# ProtoSnap-Pro_Mini.net
KiCad netlist of a schematic drawn in EAGLE
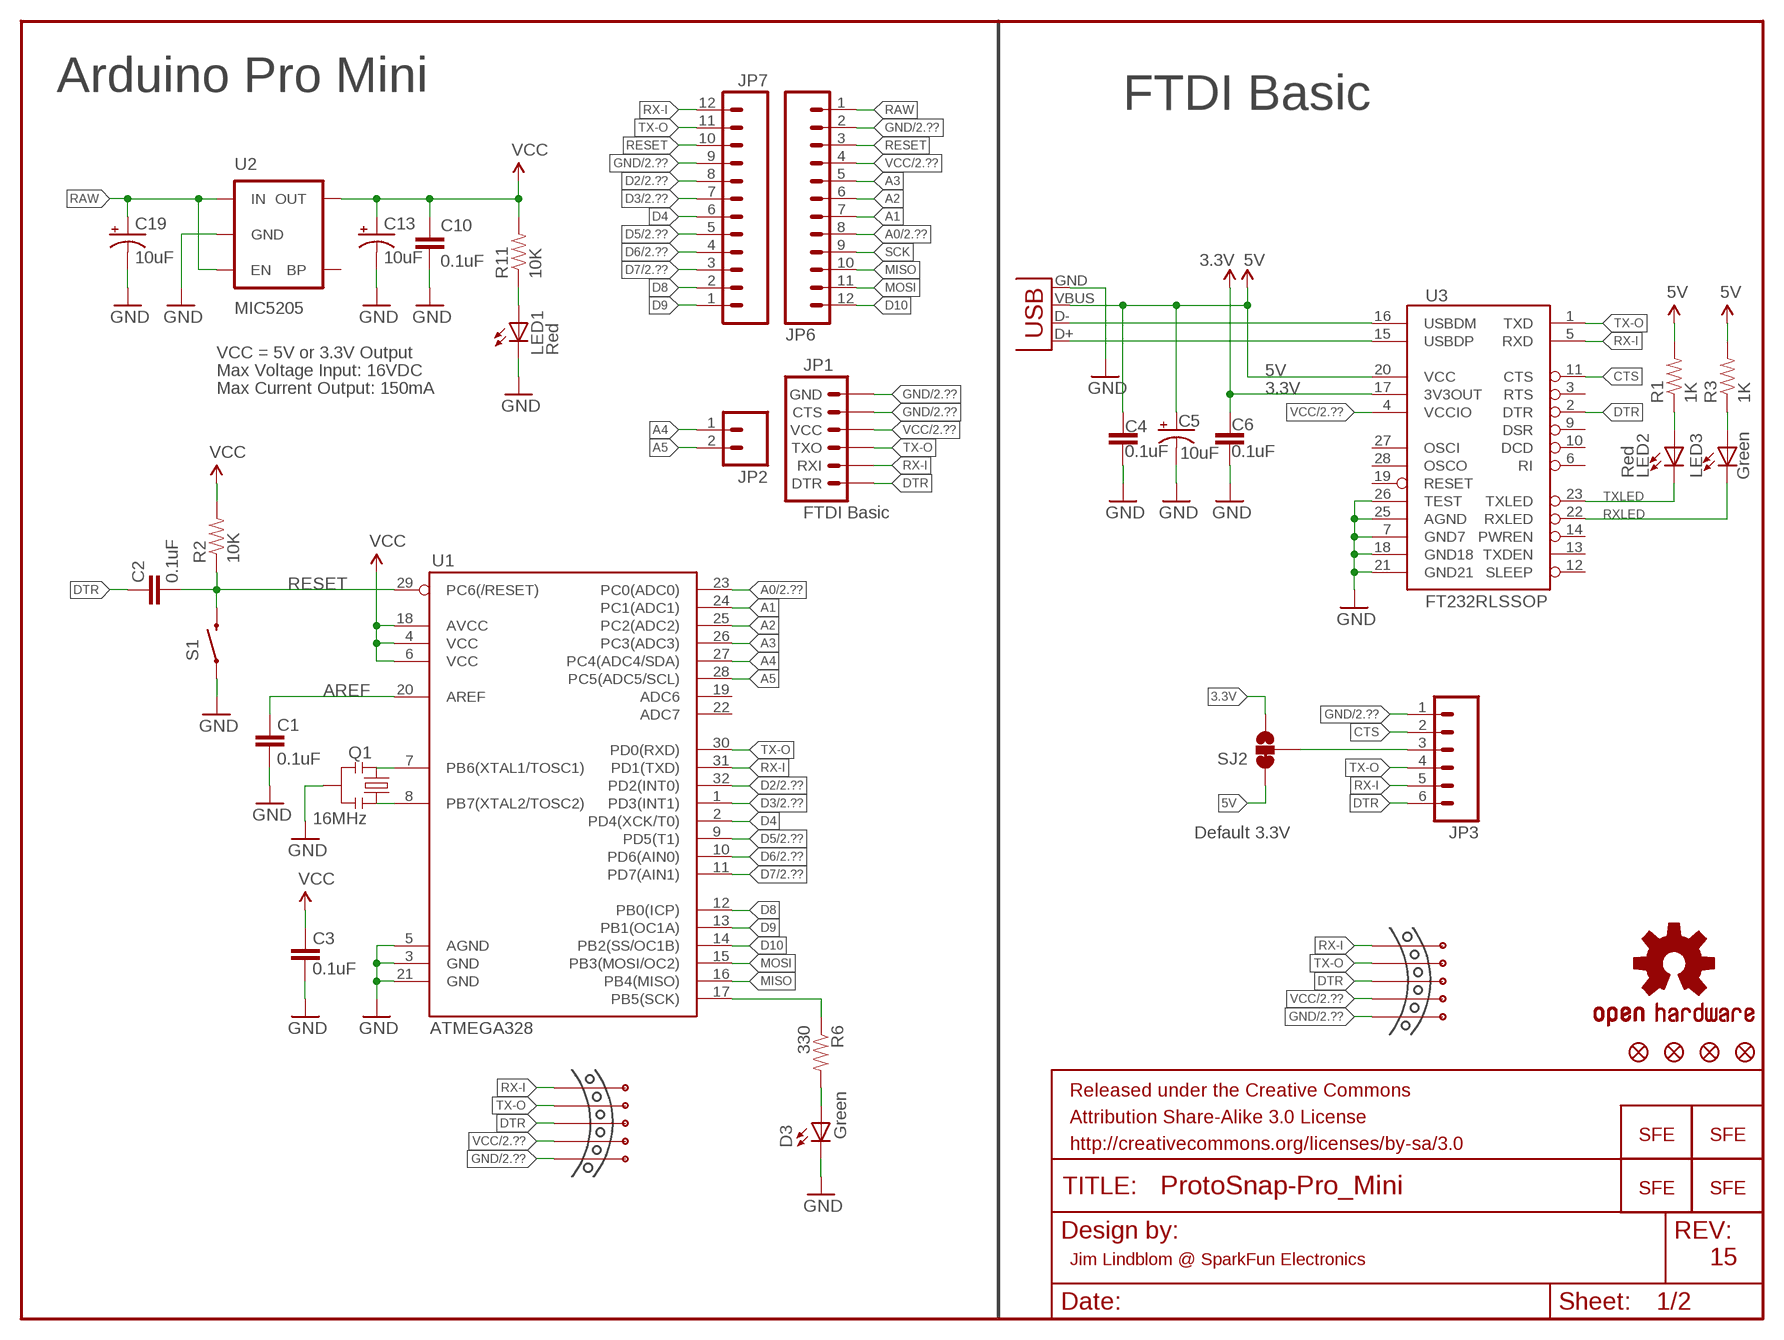
[diagram p0: schematic, sheet 1]
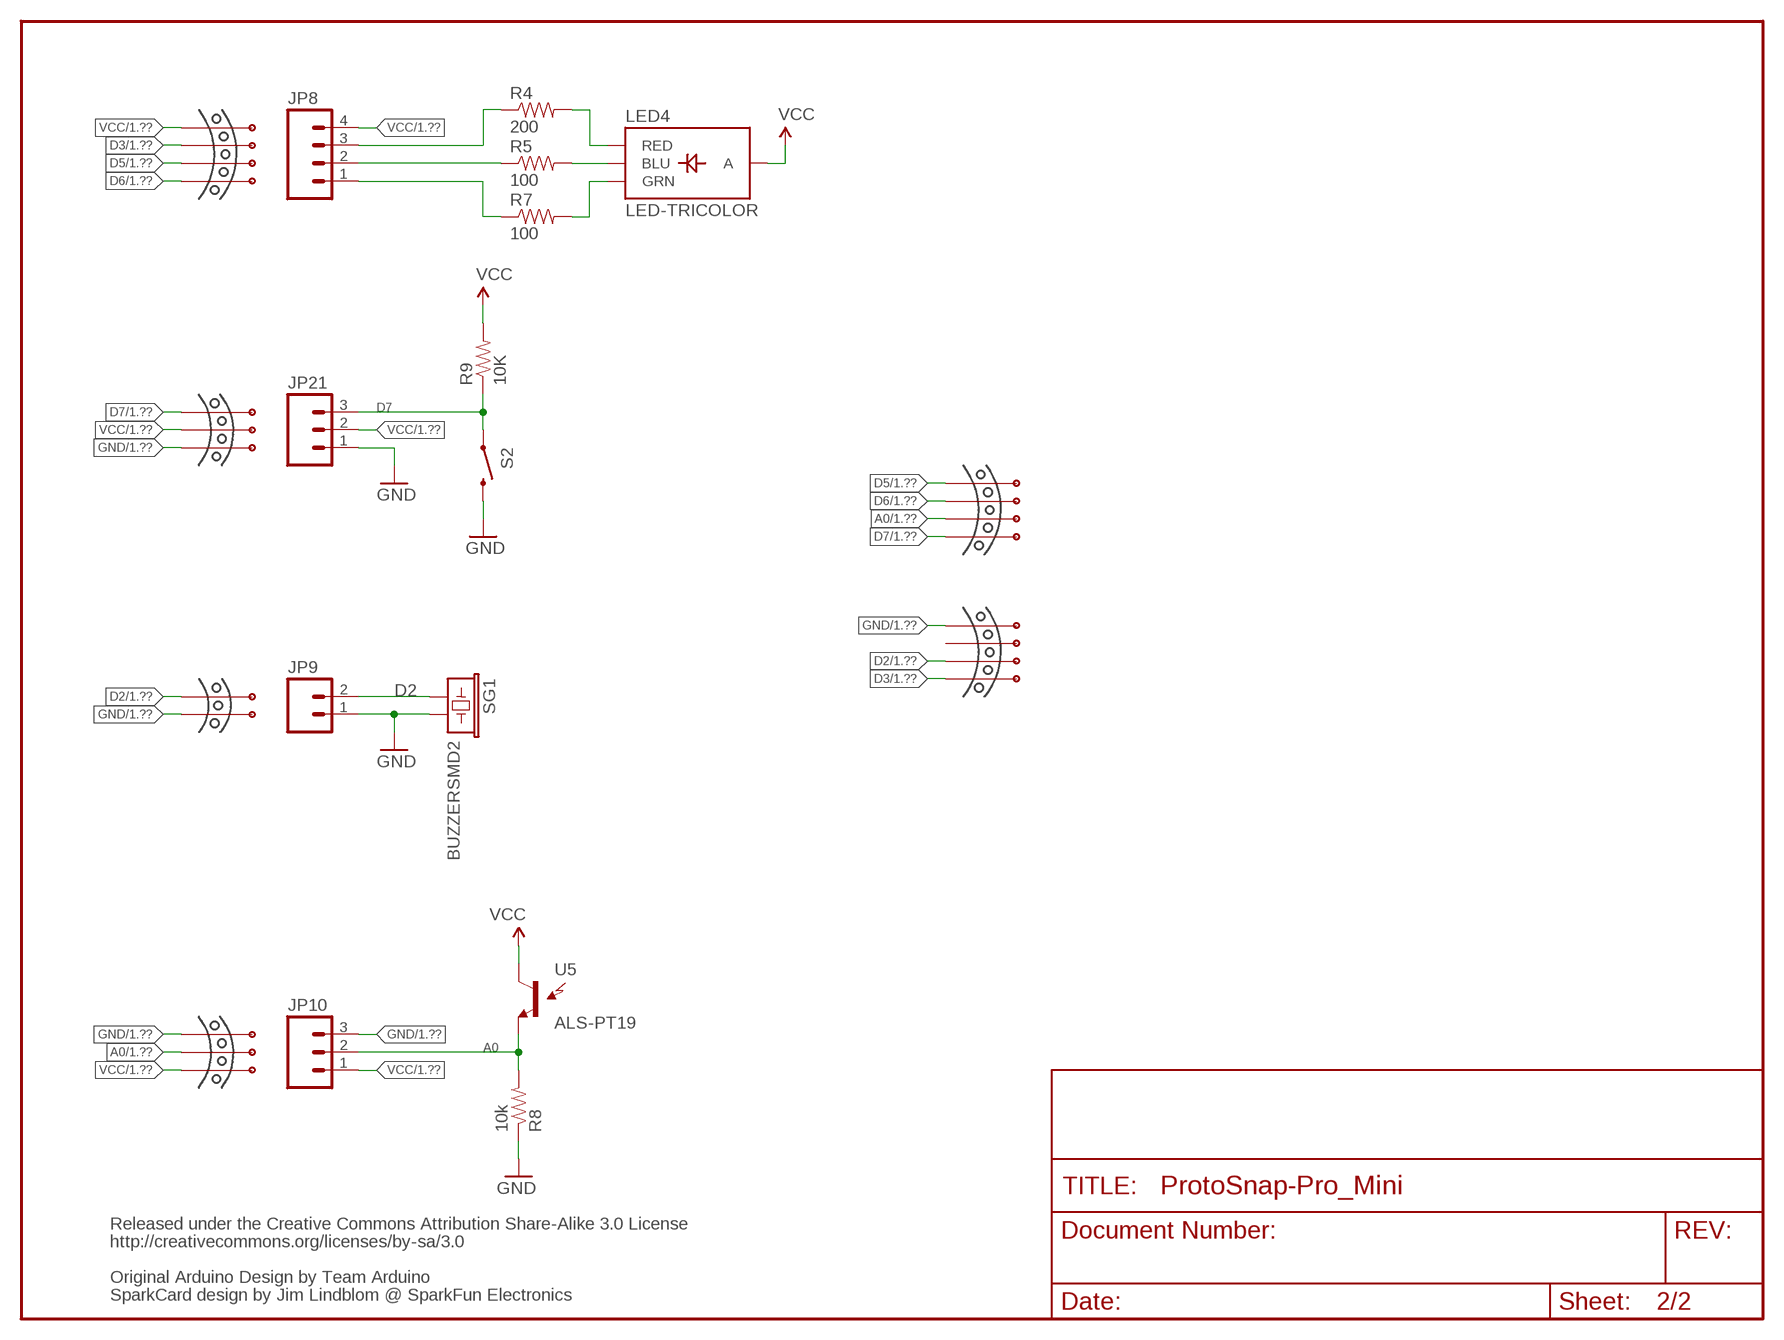
[diagram p1: schematic, sheet 2]

(export (version "E")
  (design (tool "Eeschema 10.0.6"))
  (components
    (comp (ref "C1")
      (value "0.1uF")
      (footprint "eagle-import:0603-CAP")
      (libsource (lib "eagle-import") (part "CAP0603-CAP"))
    )
    (comp (ref "C2")
      (value "0.1uF")
      (footprint "eagle-import:0603-CAP")
      (libsource (lib "eagle-import") (part "CAP0603-CAP"))
    )
    (comp (ref "C3")
      (value "0.1uF")
      (footprint "eagle-import:0603-CAP")
      (libsource (lib "eagle-import") (part "CAP0603-CAP"))
    )
    (comp (ref "C4")
      (value "0.1uF")
      (footprint "eagle-import:0603-CAP")
      (libsource (lib "eagle-import") (part "CAP0603-CAP"))
    )
    (comp (ref "C5")
      (value "10uF")
      (footprint "eagle-import:EIA3216")
      (libsource (lib "eagle-import") (part "CAP_POL1206"))
    )
    (comp (ref "C6")
      (value "0.1uF")
      (footprint "eagle-import:0603-CAP")
      (libsource (lib "eagle-import") (part "CAP0603-CAP"))
    )
    (comp (ref "C10")
      (value "0.1uF")
      (footprint "eagle-import:0603-CAP")
      (libsource (lib "eagle-import") (part "CAP0603-CAP"))
    )
    (comp (ref "C13")
      (value "10uF")
      (footprint "eagle-import:EIA3216")
      (libsource (lib "eagle-import") (part "CAP_POL1206"))
    )
    (comp (ref "C19")
      (value "10uF")
      (footprint "eagle-import:EIA3216")
      (libsource (lib "eagle-import") (part "CAP_POL1206"))
    )
    (comp (ref "D3")
      (value "Green")
      (footprint "eagle-import:0603-LED-ALT1")
      (libsource (lib "eagle-import") (part "LEDLED-ALT1"))
    )
    (comp (ref "FRAME1")
      (value "FRAME-LETTER")
      (footprint "eagle-import:CREATIVE_COMMONS")
      (libsource (lib "eagle-import") (part "SparkFun-Aesthetics_FRAME-LETTER"))
    )
    (comp (ref "JP1")
      (value "FTDI Basic")
      (footprint "eagle-import:1X06")
      (libsource (lib "eagle-import") (part "ARDUINO_SERIAL_PROGRAMPTH"))
    )
    (comp (ref "JP2")
      (value "M02PTH")
      (footprint "eagle-import:1X02")
      (libsource (lib "eagle-import") (part "M02PTH"))
    )
    (comp (ref "JP3")
      (value "M06SIP")
      (footprint "eagle-import:1X06")
      (libsource (lib "eagle-import") (part "M06SIP"))
    )
    (comp (ref "JP4")
      (value "LOGO-SFENW2")
      (footprint "eagle-import:SFE-NEW-WEB")
      (libsource (lib "eagle-import") (part "LOGO-SFENW2"))
    )
    (comp (ref "JP6")
      (value "M12PTH")
      (footprint "eagle-import:1X12")
      (libsource (lib "eagle-import") (part "M12PTH"))
    )
    (comp (ref "JP7")
      (value "M12PTH")
      (footprint "eagle-import:1X12")
      (libsource (lib "eagle-import") (part "M12PTH"))
    )
    (comp (ref "JP15")
      (value "LOGO-SFESK")
      (footprint "eagle-import:SFE-LOGO-FLAME")
      (libsource (lib "eagle-import") (part "LOGO-SFESK"))
    )
    (comp (ref "JP16")
      (value "FIDUCIAL1X2.5")
      (footprint "eagle-import:FIDUCIAL-1X2.5")
      (libsource (lib "eagle-import") (part "FIDUCIAL1X2.5"))
    )
    (comp (ref "JP17")
      (value "LOGO-SFESK")
      (footprint "eagle-import:SFE-LOGO-FLAME")
      (libsource (lib "eagle-import") (part "LOGO-SFESK"))
    )
    (comp (ref "JP18")
      (value "LOGO-SFENEW")
      (footprint "eagle-import:SFE-NEW-WEBLOGO")
      (libsource (lib "eagle-import") (part "LOGO-SFENEW"))
    )
    (comp (ref "JP19")
      (value "FIDUCIAL1X2.5")
      (footprint "eagle-import:FIDUCIAL-1X2.5")
      (libsource (lib "eagle-import") (part "FIDUCIAL1X2.5"))
    )
    (comp (ref "JP20")
      (value "FIDUCIAL1X2.5")
      (footprint "eagle-import:FIDUCIAL-1X2.5")
      (libsource (lib "eagle-import") (part "FIDUCIAL1X2.5"))
    )
    (comp (ref "JP22")
      (value "FIDUCIAL1X2.5")
      (footprint "eagle-import:FIDUCIAL-1X2.5")
      (libsource (lib "eagle-import") (part "FIDUCIAL1X2.5"))
    )
    (comp (ref "LED1")
      (value "Red")
      (footprint "eagle-import:0603-LED-ALT1")
      (libsource (lib "eagle-import") (part "LEDLED-ALT1"))
    )
    (comp (ref "LED2")
      (value "Red")
      (footprint "eagle-import:0603-LED-ALT1")
      (libsource (lib "eagle-import") (part "LEDLED-ALT1"))
    )
    (comp (ref "LED3")
      (value "Green")
      (footprint "eagle-import:0603-LED-ALT1")
      (libsource (lib "eagle-import") (part "LEDLED-ALT1"))
    )
    (comp (ref "LOGO1")
      (value "OSHW-LOGOS")
      (footprint "eagle-import:OSHW-LOGO-S")
      (libsource (lib "eagle-import") (part "OSHW-LOGOS"))
    )
    (comp (ref "Q1")
      (value "16MHz")
      (footprint "eagle-import:RESONATOR-SMD-1_1")
      (libsource (lib "eagle-import") (part "RESONATOR1{colon}1"))
    )
    (comp (ref "R1")
      (value "1K")
      (footprint "eagle-import:0603-RES")
      (libsource (lib "eagle-import") (part "RESISTOR0603-RES"))
    )
    (comp (ref "R2")
      (value "10K")
      (footprint "eagle-import:0603-RES")
      (libsource (lib "eagle-import") (part "RESISTOR0603-RES"))
    )
    (comp (ref "R3")
      (value "1K")
      (footprint "eagle-import:0603-RES")
      (libsource (lib "eagle-import") (part "RESISTOR0603-RES"))
    )
    (comp (ref "R6")
      (value "330")
      (footprint "eagle-import:0603-RES")
      (libsource (lib "eagle-import") (part "RESISTOR0603-RES"))
    )
    (comp (ref "R11")
      (value "10K")
      (footprint "eagle-import:0603-RES")
      (libsource (lib "eagle-import") (part "RESISTOR0603-RES"))
    )
    (comp (ref "S1")
      (value "SWITCH-MOMENTARY-2SMD-ALT01")
      (footprint "eagle-import:TACTILE-SWITCH-SMD-ALT01")
      (libsource (lib "eagle-import") (part "SWITCH-MOMENTARY-2SMD-ALT01"))
    )
    (comp (ref "SJ2")
      (value "SOLDERJUMPER_2WAYS")
      (footprint "eagle-import:SJ_3")
      (libsource (lib "eagle-import") (part "SOLDERJUMPER_2WAYS"))
    )
    (comp (ref "U$22")
      (value "MOUSE-BITE-5")
      (footprint "eagle-import:MOUSE-BITE-5")
      (libsource (lib "eagle-import") (part "MOUSE-BITE-5"))
    )
    (comp (ref "U$23")
      (value "MOUSE-BITE-5")
      (footprint "eagle-import:MOUSE-BITE-5")
      (libsource (lib "eagle-import") (part "MOUSE-BITE-5"))
    )
    (comp (ref "U1")
      (value "ATMEGA328")
      (footprint "eagle-import:TQFP32-08")
      (libsource (lib "eagle-import") (part "ATMEGA168"))
    )
    (comp (ref "U2")
      (value "MIC5205")
      (footprint "eagle-import:SOT23-5")
      (libsource (lib "eagle-import") (part "V_REG_LDOSMD"))
    )
    (comp (ref "U3")
      (value "FT232RLSSOP")
      (footprint "eagle-import:SSOP28DB")
      (libsource (lib "eagle-import") (part "FT232RLSSOP"))
    )
    (comp (ref "X2")
      (value "USB-SMD-NS")
      (footprint "eagle-import:USB-MINIB-NOSTOP")
      (libsource (lib "eagle-import") (part "USB-SMD-NS"))
    )
    (comp (ref "JP8")
      (value "M04PTH")
      (footprint "eagle-import:1X04")
      (libsource (lib "eagle-import") (part "M04PTH"))
    )
    (comp (ref "JP9")
      (value "M02PTH")
      (footprint "eagle-import:1X02")
      (libsource (lib "eagle-import") (part "M02PTH"))
    )
    (comp (ref "JP10")
      (value "M03PTH")
      (footprint "eagle-import:1X03")
      (libsource (lib "eagle-import") (part "M03PTH"))
    )
    (comp (ref "JP21")
      (value "M03PTH")
      (footprint "eagle-import:1X03")
      (libsource (lib "eagle-import") (part "M03PTH"))
    )
    (comp (ref "LED4")
      (value "LED-TRICOLOR")
      (footprint "eagle-import:LED-TRICOLOR-SMD")
      (libsource (lib "eagle-import") (part "LED-TRICOLOR"))
    )
    (comp (ref "R4")
      (value "200")
      (footprint "eagle-import:0603-RES")
      (libsource (lib "eagle-import") (part "RESISTOR0603-RES"))
    )
    (comp (ref "R5")
      (value "100")
      (footprint "eagle-import:0603-RES")
      (libsource (lib "eagle-import") (part "RESISTOR0603-RES"))
    )
    (comp (ref "R7")
      (value "100")
      (footprint "eagle-import:0603-RES")
      (libsource (lib "eagle-import") (part "RESISTOR0603-RES"))
    )
    (comp (ref "R8")
      (value "10k")
      (footprint "eagle-import:0603-RES")
      (libsource (lib "eagle-import") (part "RESISTOR0603-RES"))
    )
    (comp (ref "R9")
      (value "10K")
      (footprint "eagle-import:0603-RES")
      (libsource (lib "eagle-import") (part "RESISTOR0603-RES"))
    )
    (comp (ref "S2")
      (value "SWITCH-MOMENTARY-2SMD-ALT01")
      (footprint "eagle-import:TACTILE-SWITCH-SMD-ALT01")
      (libsource (lib "eagle-import") (part "SWITCH-MOMENTARY-2SMD-ALT01"))
    )
    (comp (ref "SG1")
      (value "BUZZERSMD2")
      (footprint "eagle-import:BUZZER-CCV")
      (libsource (lib "eagle-import") (part "BUZZERSMD2"))
    )
    (comp (ref "U$2")
      (value "MOUSE-BITE-3")
      (footprint "eagle-import:MOUSE-BITE-3")
      (libsource (lib "eagle-import") (part "MOUSE-BITE-3"))
    )
    (comp (ref "U$7")
      (value "MOUSE-BITE-2")
      (footprint "eagle-import:MOUSE-BITE-2")
      (libsource (lib "eagle-import") (part "MOUSE-BITE-2"))
    )
    (comp (ref "U$8")
      (value "MOUSE-BITE-4")
      (footprint "eagle-import:MOUSE-BITE-4")
      (libsource (lib "eagle-import") (part "MOUSE-BITE-4"))
    )
    (comp (ref "U$9")
      (value "MOUSE-BITE-3")
      (footprint "eagle-import:MOUSE-BITE-3")
      (libsource (lib "eagle-import") (part "MOUSE-BITE-3"))
    )
    (comp (ref "U$13")
      (value "MOUSE-BITE-4")
      (footprint "eagle-import:MOUSE-BITE-4")
      (libsource (lib "eagle-import") (part "MOUSE-BITE-4"))
    )
    (comp (ref "U$14")
      (value "MOUSE-BITE-4")
      (footprint "eagle-import:MOUSE-BITE-4")
      (libsource (lib "eagle-import") (part "MOUSE-BITE-4"))
    )
    (comp (ref "U5")
      (value "ALS-PT19")
      (footprint "eagle-import:ALS-PT19")
      (libsource (lib "eagle-import") (part "LIGHTSENSORALS"))
    )
  )
  (nets
    (net (code "1") (name "3.3V") (class "Default")
      (node (ref "C6") (pin "1") (pinfunction "1_1") (pintype "passive"))
      (node (ref "SJ2") (pin "3") (pinfunction "3_3") (pintype "passive"))
      (node (ref "U3") (pin "17") (pinfunction "3V3OUT_17") (pintype "output"))
    )
    (net (code "2") (name "5V") (class "Default")
      (node (ref "C4") (pin "1") (pinfunction "1_1") (pintype "passive"))
      (node (ref "C5") (pin "A") (pinfunction "+_A") (pintype "passive"))
      (node (ref "R1") (pin "2") (pinfunction "2_2") (pintype "passive"))
      (node (ref "R3") (pin "2") (pinfunction "2_2") (pintype "passive"))
      (node (ref "SJ2") (pin "1") (pinfunction "1_1") (pintype "passive"))
      (node (ref "U3") (pin "20") (pinfunction "VCC_20") (pintype "power_in"))
      (node (ref "X2") (pin "VBUS") (pinfunction "VBUS_VBUS") (pintype "bidirectional"))
    )
    (net (code "3") (name "A0") (class "Default")
      (node (ref "JP10") (pin "2") (pinfunction "2_2") (pintype "passive"))
      (node (ref "JP6") (pin "8") (pinfunction "8_8") (pintype "passive"))
      (node (ref "R8") (pin "2") (pinfunction "2_2") (pintype "passive"))
      (node (ref "U$13") (pin "P$3") (pinfunction "P$3_P$3") (pintype "bidirectional"))
      (node (ref "U$9") (pin "P$2") (pinfunction "P$2_P$2") (pintype "bidirectional"))
      (node (ref "U1") (pin "23") (pinfunction "PC0(ADC0)_23") (pintype "bidirectional"))
      (node (ref "U5") (pin "E") (pinfunction "E1_E") (pintype "passive"))
    )
    (net (code "4") (name "A1") (class "Default")
      (node (ref "JP6") (pin "7") (pinfunction "7_7") (pintype "passive"))
      (node (ref "U1") (pin "24") (pinfunction "PC1(ADC1)_24") (pintype "bidirectional"))
    )
    (net (code "5") (name "A2") (class "Default")
      (node (ref "JP6") (pin "6") (pinfunction "6_6") (pintype "passive"))
      (node (ref "U1") (pin "25") (pinfunction "PC2(ADC2)_25") (pintype "bidirectional"))
    )
    (net (code "6") (name "A3") (class "Default")
      (node (ref "JP6") (pin "5") (pinfunction "5_5") (pintype "passive"))
      (node (ref "U1") (pin "26") (pinfunction "PC3(ADC3)_26") (pintype "bidirectional"))
    )
    (net (code "7") (name "A4") (class "Default")
      (node (ref "JP2") (pin "1") (pinfunction "1_1") (pintype "passive"))
      (node (ref "U1") (pin "27") (pinfunction "PC4(ADC4/SDA)_27") (pintype "bidirectional"))
    )
    (net (code "8") (name "A5") (class "Default")
      (node (ref "JP2") (pin "2") (pinfunction "2_2") (pintype "passive"))
      (node (ref "U1") (pin "28") (pinfunction "PC5(ADC5/SCL)_28") (pintype "bidirectional"))
    )
    (net (code "9") (name "AREF") (class "Default")
      (node (ref "C1") (pin "2") (pinfunction "2_2") (pintype "passive"))
      (node (ref "U1") (pin "20") (pinfunction "AREF_20") (pintype "bidirectional"))
    )
    (net (code "10") (name "CTS") (class "Default")
      (node (ref "JP3") (pin "2") (pinfunction "2_2") (pintype "passive"))
      (node (ref "U3") (pin "11") (pinfunction "CTS_11") (pintype "input"))
    )
    (net (code "11") (name "D2") (class "Default")
      (node (ref "JP7") (pin "8") (pinfunction "8_8") (pintype "passive"))
      (node (ref "JP9") (pin "2") (pinfunction "2_2") (pintype "passive"))
      (node (ref "SG1") (pin "+") (pinfunction "1_+") (pintype "passive"))
      (node (ref "U$14") (pin "P$3") (pinfunction "P$3_P$3") (pintype "bidirectional"))
      (node (ref "U$7") (pin "P$1") (pinfunction "P$1_P$1") (pintype "bidirectional"))
      (node (ref "U1") (pin "32") (pinfunction "PD2(INT0)_32") (pintype "bidirectional"))
    )
    (net (code "12") (name "D3") (class "Default")
      (node (ref "JP7") (pin "7") (pinfunction "7_7") (pintype "passive"))
      (node (ref "JP8") (pin "3") (pinfunction "3_3") (pintype "passive"))
      (node (ref "R4") (pin "1") (pinfunction "1_1") (pintype "passive"))
      (node (ref "U$14") (pin "P$4") (pinfunction "P$4_P$4") (pintype "bidirectional"))
      (node (ref "U$8") (pin "P$2") (pinfunction "P$2_P$2") (pintype "bidirectional"))
      (node (ref "U1") (pin "1") (pinfunction "PD3(INT1)_1") (pintype "bidirectional"))
    )
    (net (code "13") (name "D4") (class "Default")
      (node (ref "JP7") (pin "6") (pinfunction "6_6") (pintype "passive"))
      (node (ref "U1") (pin "2") (pinfunction "PD4(XCK/T0)_2") (pintype "bidirectional"))
    )
    (net (code "14") (name "D5") (class "Default")
      (node (ref "JP7") (pin "5") (pinfunction "5_5") (pintype "passive"))
      (node (ref "JP8") (pin "1") (pinfunction "1_1") (pintype "passive"))
      (node (ref "R7") (pin "1") (pinfunction "1_1") (pintype "passive"))
      (node (ref "U$13") (pin "P$1") (pinfunction "P$1_P$1") (pintype "bidirectional"))
      (node (ref "U$8") (pin "P$3") (pinfunction "P$3_P$3") (pintype "bidirectional"))
      (node (ref "U1") (pin "9") (pinfunction "PD5(T1)_9") (pintype "bidirectional"))
    )
    (net (code "15") (name "D6") (class "Default")
      (node (ref "JP7") (pin "4") (pinfunction "4_4") (pintype "passive"))
      (node (ref "JP8") (pin "2") (pinfunction "2_2") (pintype "passive"))
      (node (ref "R5") (pin "1") (pinfunction "1_1") (pintype "passive"))
      (node (ref "U$13") (pin "P$2") (pinfunction "P$2_P$2") (pintype "bidirectional"))
      (node (ref "U$8") (pin "P$4") (pinfunction "P$4_P$4") (pintype "bidirectional"))
      (node (ref "U1") (pin "10") (pinfunction "PD6(AIN0)_10") (pintype "bidirectional"))
    )
    (net (code "16") (name "D7") (class "Default")
      (node (ref "JP21") (pin "3") (pinfunction "3_3") (pintype "passive"))
      (node (ref "JP7") (pin "3") (pinfunction "3_3") (pintype "passive"))
      (node (ref "R9") (pin "1") (pinfunction "1_1") (pintype "passive"))
      (node (ref "S2") (pin "1") (pinfunction "1_1") (pintype "passive"))
      (node (ref "S2") (pin "2") (pinfunction "1_2") (pintype "passive"))
      (node (ref "U$13") (pin "P$4") (pinfunction "P$4_P$4") (pintype "bidirectional"))
      (node (ref "U$2") (pin "P$3") (pinfunction "P$3_P$3") (pintype "bidirectional"))
      (node (ref "U1") (pin "11") (pinfunction "PD7(AIN1)_11") (pintype "bidirectional"))
    )
    (net (code "17") (name "D8") (class "Default")
      (node (ref "JP7") (pin "2") (pinfunction "2_2") (pintype "passive"))
      (node (ref "U1") (pin "12") (pinfunction "PB0(ICP)_12") (pintype "bidirectional"))
    )
    (net (code "18") (name "D9") (class "Default")
      (node (ref "JP7") (pin "1") (pinfunction "1_1") (pintype "passive"))
      (node (ref "U1") (pin "13") (pinfunction "PB1(OC1A)_13") (pintype "bidirectional"))
    )
    (net (code "19") (name "D10") (class "Default")
      (node (ref "JP6") (pin "12") (pinfunction "12_12") (pintype "passive"))
      (node (ref "U1") (pin "14") (pinfunction "PB2(SS/OC1B)_14") (pintype "bidirectional"))
    )
    (net (code "20") (name "DTR") (class "Default")
      (node (ref "C2") (pin "2") (pinfunction "2_2") (pintype "passive"))
      (node (ref "JP1") (pin "1") (pinfunction "DTR_1") (pintype "passive"))
      (node (ref "JP3") (pin "6") (pinfunction "6_6") (pintype "passive"))
      (node (ref "U$22") (pin "P$3") (pinfunction "P$3_P$3") (pintype "bidirectional"))
      (node (ref "U$23") (pin "P$3") (pinfunction "P$3_P$3") (pintype "bidirectional"))
      (node (ref "U3") (pin "2") (pinfunction "DTR_2") (pintype "output"))
    )
    (net (code "21") (name "GND") (class "Default")
      (node (ref "C1") (pin "1") (pinfunction "1_1") (pintype "passive"))
      (node (ref "C10") (pin "2") (pinfunction "2_2") (pintype "passive"))
      (node (ref "C13") (pin "C") (pinfunction "-_C") (pintype "passive"))
      (node (ref "C19") (pin "C") (pinfunction "-_C") (pintype "passive"))
      (node (ref "C3") (pin "1") (pinfunction "1_1") (pintype "passive"))
      (node (ref "C4") (pin "2") (pinfunction "2_2") (pintype "passive"))
      (node (ref "C5") (pin "C") (pinfunction "-_C") (pintype "passive"))
      (node (ref "C6") (pin "2") (pinfunction "2_2") (pintype "passive"))
      (node (ref "D3") (pin "C") (pinfunction "C_C") (pintype "passive"))
      (node (ref "JP1") (pin "5") (pinfunction "CTS_5") (pintype "passive"))
      (node (ref "JP1") (pin "6") (pinfunction "GND_6") (pintype "passive"))
      (node (ref "JP10") (pin "3") (pinfunction "3_3") (pintype "passive"))
      (node (ref "JP21") (pin "1") (pinfunction "1_1") (pintype "passive"))
      (node (ref "JP3") (pin "1") (pinfunction "1_1") (pintype "passive"))
      (node (ref "JP6") (pin "2") (pinfunction "2_2") (pintype "passive"))
      (node (ref "JP7") (pin "9") (pinfunction "9_9") (pintype "passive"))
      (node (ref "JP9") (pin "1") (pinfunction "1_1") (pintype "passive"))
      (node (ref "LED1") (pin "C") (pinfunction "C_C") (pintype "passive"))
      (node (ref "Q1") (pin "2") (pinfunction "2_2") (pintype "passive"))
      (node (ref "R8") (pin "1") (pinfunction "1_1") (pintype "passive"))
      (node (ref "S1") (pin "1") (pinfunction "1_1") (pintype "passive"))
      (node (ref "S1") (pin "2") (pinfunction "1_2") (pintype "passive"))
      (node (ref "S2") (pin "3") (pinfunction "2_3") (pintype "passive"))
      (node (ref "S2") (pin "4") (pinfunction "2_4") (pintype "passive"))
      (node (ref "SG1") (pin "-") (pinfunction "2_-") (pintype "passive"))
      (node (ref "U$14") (pin "P$1") (pinfunction "P$1_P$1") (pintype "bidirectional"))
      (node (ref "U$2") (pin "P$1") (pinfunction "P$1_P$1") (pintype "bidirectional"))
      (node (ref "U$22") (pin "P$5") (pinfunction "P$5_P$5") (pintype "bidirectional"))
      (node (ref "U$23") (pin "P$5") (pinfunction "P$5_P$5") (pintype "bidirectional"))
      (node (ref "U$7") (pin "P$2") (pinfunction "P$2_P$2") (pintype "bidirectional"))
      (node (ref "U$9") (pin "P$3") (pinfunction "P$3_P$3") (pintype "bidirectional"))
      (node (ref "U1") (pin "21") (pinfunction "GND_21") (pintype "bidirectional"))
      (node (ref "U1") (pin "3") (pinfunction "GND_3") (pintype "bidirectional"))
      (node (ref "U1") (pin "5") (pinfunction "AGND_5") (pintype "bidirectional"))
      (node (ref "U2") (pin "2") (pinfunction "GND_2") (pintype "input"))
      (node (ref "U3") (pin "18") (pinfunction "GND18_18") (pintype "power_in"))
      (node (ref "U3") (pin "21") (pinfunction "GND21_21") (pintype "power_in"))
      (node (ref "U3") (pin "25") (pinfunction "AGND_25") (pintype "power_in"))
      (node (ref "U3") (pin "26") (pinfunction "TEST_26") (pintype "input"))
      (node (ref "U3") (pin "7") (pinfunction "GND7_7") (pintype "power_in"))
      (node (ref "X2") (pin "GND") (pinfunction "GND_GND") (pintype "bidirectional"))
    )
    (net (code "22") (name "MISO") (class "Default")
      (node (ref "JP6") (pin "10") (pinfunction "10_10") (pintype "passive"))
      (node (ref "U1") (pin "16") (pinfunction "PB4(MISO)_16") (pintype "bidirectional"))
    )
    (net (code "23") (name "MOSI") (class "Default")
      (node (ref "JP6") (pin "11") (pinfunction "11_11") (pintype "passive"))
      (node (ref "U1") (pin "15") (pinfunction "PB3(MOSI/OC2)_15") (pintype "bidirectional"))
    )
    (net (code "24") (name "Net-(D3-PadA)") (class "Default")
      (node (ref "D3") (pin "A") (pinfunction "A_A") (pintype "passive"))
      (node (ref "R6") (pin "2") (pinfunction "2_2") (pintype "passive"))
    )
    (net (code "25") (name "Net-(LED1-PadA)") (class "Default")
      (node (ref "LED1") (pin "A") (pinfunction "A_A") (pintype "passive"))
      (node (ref "R11") (pin "1") (pinfunction "1_1") (pintype "passive"))
    )
    (net (code "26") (name "Net-(LED2-PadA)") (class "Default")
      (node (ref "LED2") (pin "A") (pinfunction "A_A") (pintype "passive"))
      (node (ref "R1") (pin "1") (pinfunction "1_1") (pintype "passive"))
    )
    (net (code "27") (name "Net-(LED3-PadA)") (class "Default")
      (node (ref "LED3") (pin "A") (pinfunction "A_A") (pintype "passive"))
      (node (ref "R3") (pin "1") (pinfunction "1_1") (pintype "passive"))
    )
    (net (code "28") (name "Net-(LED4-BLU)") (class "Default")
      (node (ref "LED4") (pin "B") (pinfunction "BLU_B") (pintype "bidirectional"))
      (node (ref "R5") (pin "2") (pinfunction "2_2") (pintype "passive"))
    )
    (net (code "29") (name "Net-(LED4-GRN)") (class "Default")
      (node (ref "LED4") (pin "G") (pinfunction "GRN_G") (pintype "bidirectional"))
      (node (ref "R7") (pin "2") (pinfunction "2_2") (pintype "passive"))
    )
    (net (code "30") (name "Net-(LED4-RED)") (class "Default")
      (node (ref "LED4") (pin "R") (pinfunction "RED_R") (pintype "bidirectional"))
      (node (ref "R4") (pin "2") (pinfunction "2_2") (pintype "passive"))
    )
    (net (code "31") (name "Net-(U1-PB6(XTAL1{slash}TOSC1))") (class "Default")
      (node (ref "Q1") (pin "3") (pinfunction "3_3") (pintype "passive"))
      (node (ref "U1") (pin "7") (pinfunction "PB6(XTAL1/TOSC1)_7") (pintype "bidirectional"))
    )
    (net (code "32") (name "Net-(U1-PB7(XTAL2{slash}TOSC2))") (class "Default")
      (node (ref "Q1") (pin "1") (pinfunction "1_1") (pintype "passive"))
      (node (ref "U1") (pin "8") (pinfunction "PB7(XTAL2/TOSC2)_8") (pintype "bidirectional"))
    )
    (net (code "33") (name "Net-(U3-USBDM)") (class "Default")
      (node (ref "U3") (pin "16") (pinfunction "USBDM_16") (pintype "bidirectional"))
      (node (ref "X2") (pin "D-") (pinfunction "D-_D-") (pintype "bidirectional"))
    )
    (net (code "34") (name "Net-(U3-USBDP)") (class "Default")
      (node (ref "U3") (pin "15") (pinfunction "USBDP_15") (pintype "bidirectional"))
      (node (ref "X2") (pin "D+") (pinfunction "D+_D+") (pintype "bidirectional"))
    )
    (net (code "35") (name "RAW") (class "Default")
      (node (ref "C19") (pin "A") (pinfunction "+_A") (pintype "passive"))
      (node (ref "JP6") (pin "1") (pinfunction "1_1") (pintype "passive"))
      (node (ref "U2") (pin "1") (pinfunction "IN_1") (pintype "input"))
      (node (ref "U2") (pin "3") (pinfunction "EN_3") (pintype "input"))
    )
    (net (code "36") (name "RESET") (class "Default")
      (node (ref "C2") (pin "1") (pinfunction "1_1") (pintype "passive"))
      (node (ref "JP6") (pin "3") (pinfunction "3_3") (pintype "passive"))
      (node (ref "JP7") (pin "10") (pinfunction "10_10") (pintype "passive"))
      (node (ref "R2") (pin "1") (pinfunction "1_1") (pintype "passive"))
      (node (ref "S1") (pin "3") (pinfunction "2_3") (pintype "passive"))
      (node (ref "S1") (pin "4") (pinfunction "2_4") (pintype "passive"))
      (node (ref "U1") (pin "29") (pinfunction "PC6(/RESET)_29") (pintype "bidirectional"))
    )
    (net (code "37") (name "RX-I") (class "Default")
      (node (ref "JP1") (pin "2") (pinfunction "RXI_2") (pintype "passive"))
      (node (ref "JP3") (pin "5") (pinfunction "5_5") (pintype "passive"))
      (node (ref "JP7") (pin "12") (pinfunction "12_12") (pintype "passive"))
      (node (ref "U$22") (pin "P$1") (pinfunction "P$1_P$1") (pintype "bidirectional"))
      (node (ref "U$23") (pin "P$1") (pinfunction "P$1_P$1") (pintype "bidirectional"))
      (node (ref "U1") (pin "31") (pinfunction "PD1(TXD)_31") (pintype "bidirectional"))
      (node (ref "U3") (pin "5") (pinfunction "RXD_5") (pintype "input"))
    )
    (net (code "38") (name "RXLED") (class "Default")
      (node (ref "LED3") (pin "C") (pinfunction "C_C") (pintype "passive"))
      (node (ref "U3") (pin "22") (pinfunction "RXLED_22") (pintype "input"))
    )
    (net (code "39") (name "SCK") (class "Default")
      (node (ref "JP6") (pin "9") (pinfunction "9_9") (pintype "passive"))
      (node (ref "R6") (pin "1") (pinfunction "1_1") (pintype "passive"))
      (node (ref "U1") (pin "17") (pinfunction "PB5(SCK)_17") (pintype "bidirectional"))
    )
    (net (code "40") (name "TX-O") (class "Default")
      (node (ref "JP1") (pin "3") (pinfunction "TXO_3") (pintype "passive"))
      (node (ref "JP3") (pin "4") (pinfunction "4_4") (pintype "passive"))
      (node (ref "JP7") (pin "11") (pinfunction "11_11") (pintype "passive"))
      (node (ref "U$22") (pin "P$2") (pinfunction "P$2_P$2") (pintype "bidirectional"))
      (node (ref "U$23") (pin "P$2") (pinfunction "P$2_P$2") (pintype "bidirectional"))
      (node (ref "U1") (pin "30") (pinfunction "PD0(RXD)_30") (pintype "bidirectional"))
      (node (ref "U3") (pin "1") (pinfunction "TXD_1") (pintype "output"))
    )
    (net (code "41") (name "TXLED") (class "Default")
      (node (ref "LED2") (pin "C") (pinfunction "C_C") (pintype "passive"))
      (node (ref "U3") (pin "23") (pinfunction "TXLED_23") (pintype "input"))
    )
    (net (code "42") (name "VCC") (class "Default")
      (node (ref "C10") (pin "1") (pinfunction "1_1") (pintype "passive"))
      (node (ref "C13") (pin "A") (pinfunction "+_A") (pintype "passive"))
      (node (ref "C3") (pin "2") (pinfunction "2_2") (pintype "passive"))
      (node (ref "JP1") (pin "4") (pinfunction "VCC_4") (pintype "passive"))
      (node (ref "JP10") (pin "1") (pinfunction "1_1") (pintype "passive"))
      (node (ref "JP21") (pin "2") (pinfunction "2_2") (pintype "passive"))
      (node (ref "JP3") (pin "3") (pinfunction "3_3") (pintype "passive"))
      (node (ref "JP6") (pin "4") (pinfunction "4_4") (pintype "passive"))
      (node (ref "JP8") (pin "4") (pinfunction "4_4") (pintype "passive"))
      (node (ref "LED4") (pin "A") (pinfunction "A_A") (pintype "bidirectional"))
      (node (ref "R11") (pin "2") (pinfunction "2_2") (pintype "passive"))
      (node (ref "R2") (pin "2") (pinfunction "2_2") (pintype "passive"))
      (node (ref "R9") (pin "2") (pinfunction "2_2") (pintype "passive"))
      (node (ref "SJ2") (pin "2") (pinfunction "2_2") (pintype "passive"))
      (node (ref "U$2") (pin "P$2") (pinfunction "P$2_P$2") (pintype "bidirectional"))
      (node (ref "U$22") (pin "P$4") (pinfunction "P$4_P$4") (pintype "bidirectional"))
      (node (ref "U$23") (pin "P$4") (pinfunction "P$4_P$4") (pintype "bidirectional"))
      (node (ref "U$8") (pin "P$1") (pinfunction "P$1_P$1") (pintype "bidirectional"))
      (node (ref "U$9") (pin "P$1") (pinfunction "P$1_P$1") (pintype "bidirectional"))
      (node (ref "U1") (pin "18") (pinfunction "AVCC_18") (pintype "bidirectional"))
      (node (ref "U1") (pin "4") (pinfunction "VCC_4") (pintype "bidirectional"))
      (node (ref "U1") (pin "6") (pinfunction "VCC_6") (pintype "bidirectional"))
      (node (ref "U2") (pin "5") (pinfunction "OUT_5") (pintype "passive"))
      (node (ref "U3") (pin "4") (pinfunction "VCCIO_4") (pintype "power_in"))
      (node (ref "U5") (pin "C") (pinfunction "C1_C") (pintype "passive"))
    )
    (net (code "43") (name "unconnected-(U$14-PadP$2)") (class "Default")
      (node (ref "U$14") (pin "P$2") (pinfunction "P$2_P$2") (pintype "bidirectional"))
    )
    (net (code "44") (name "unconnected-(U1-ADC6-Pad19)") (class "Default")
      (node (ref "U1") (pin "19") (pinfunction "ADC6_19") (pintype "bidirectional"))
    )
    (net (code "45") (name "unconnected-(U1-ADC7-Pad22)") (class "Default")
      (node (ref "U1") (pin "22") (pinfunction "ADC7_22") (pintype "bidirectional"))
    )
    (net (code "46") (name "unconnected-(U2-BP-Pad4)") (class "Default")
      (node (ref "U2") (pin "4") (pinfunction "BP_4") (pintype "input"))
    )
    (net (code "47") (name "unconnected-(U3-DCD-Pad10)") (class "Default")
      (node (ref "U3") (pin "10") (pinfunction "DCD_10") (pintype "input"))
    )
    (net (code "48") (name "unconnected-(U3-DSR-Pad9)") (class "Default")
      (node (ref "U3") (pin "9") (pinfunction "DSR_9") (pintype "input"))
    )
    (net (code "49") (name "unconnected-(U3-OSCI-Pad27)") (class "Default")
      (node (ref "U3") (pin "27") (pinfunction "OSCI_27") (pintype "input"))
    )
    (net (code "50") (name "unconnected-(U3-OSCO-Pad28)") (class "Default")
      (node (ref "U3") (pin "28") (pinfunction "OSCO_28") (pintype "output"))
    )
    (net (code "51") (name "unconnected-(U3-PWREN-Pad14)") (class "Default")
      (node (ref "U3") (pin "14") (pinfunction "PWREN_14") (pintype "input"))
    )
    (net (code "52") (name "unconnected-(U3-RESET-Pad19)") (class "Default")
      (node (ref "U3") (pin "19") (pinfunction "RESET_19") (pintype "input"))
    )
    (net (code "53") (name "unconnected-(U3-RI-Pad6)") (class "Default")
      (node (ref "U3") (pin "6") (pinfunction "RI_6") (pintype "input"))
    )
    (net (code "54") (name "unconnected-(U3-RTS-Pad3)") (class "Default")
      (node (ref "U3") (pin "3") (pinfunction "RTS_3") (pintype "output"))
    )
    (net (code "55") (name "unconnected-(U3-SLEEP-Pad12)") (class "Default")
      (node (ref "U3") (pin "12") (pinfunction "SLEEP_12") (pintype "input"))
    )
    (net (code "56") (name "unconnected-(U3-TXDEN-Pad13)") (class "Default")
      (node (ref "U3") (pin "13") (pinfunction "TXDEN_13") (pintype "input"))
    )
  )
)
